# M903X.net
KiCad netlist of a schematic drawn in EAGLE
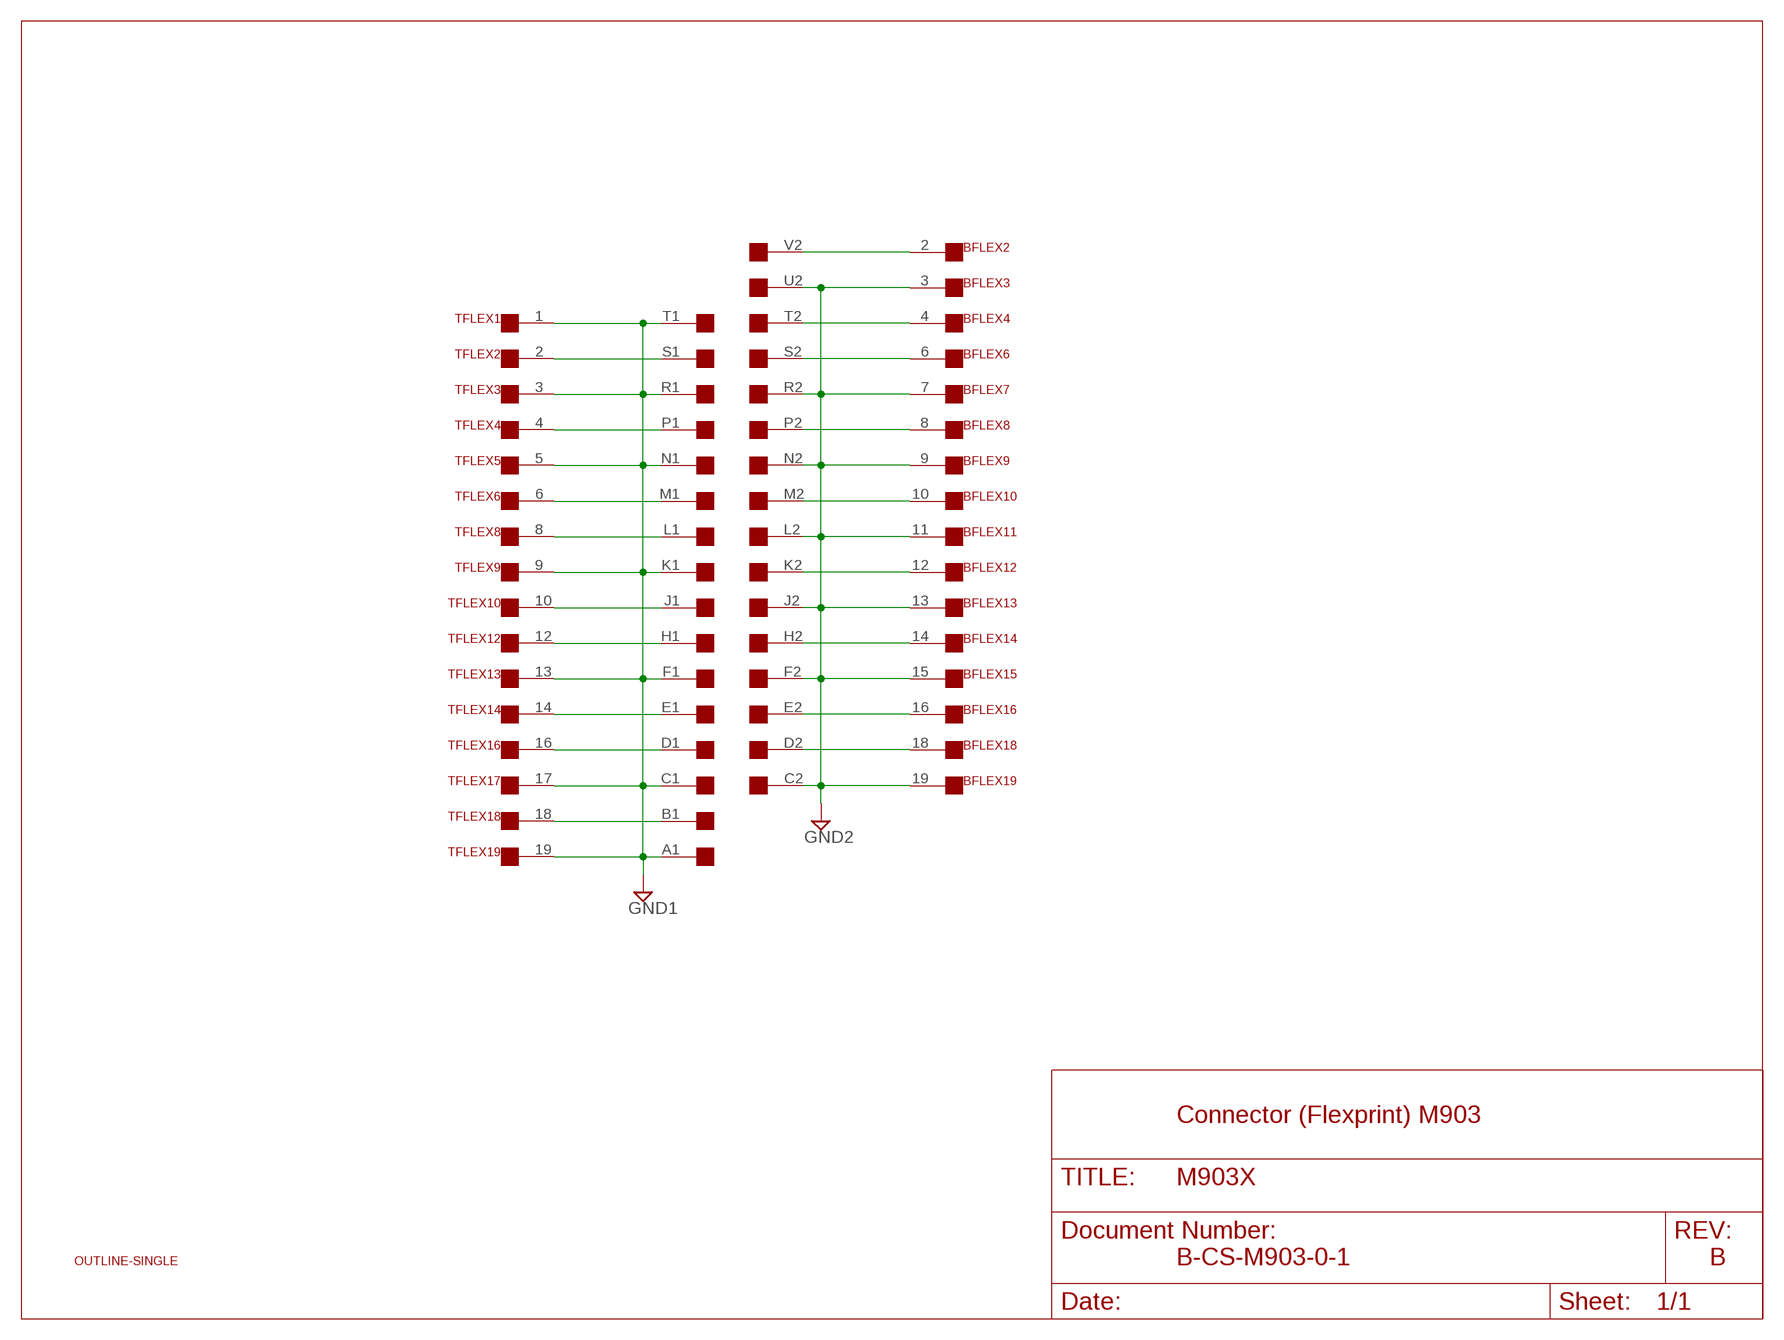
[diagram p0: schematic, sheet 1]

(export (version "E")
  (design (tool "Eeschema 10.0.6"))
  (components
    (comp (ref "BFLEX")
      (value "FLEX19")
      (footprint "eagle-import:FLEX19")
      (libsource (lib "eagle-import") (part "FLEX19"))
    )
    (comp (ref "TFLEX")
      (value "FLEX19")
      (footprint "eagle-import:FLEX19")
      (libsource (lib "eagle-import") (part "FLEX19"))
    )
    (comp (ref "U$1")
      (value "SINGLE")
      (footprint "eagle-import:EDGE-CON2")
      (libsource (lib "eagle-import") (part "SINGLE"))
    )
    (comp (ref "U$2")
      (value "OUTLINE-SINGLE")
      (footprint "eagle-import:SINGLE")
      (libsource (lib "eagle-import") (part "OUTLINE-SINGLE"))
    )
  )
  (nets
    (net (code "1") (name "GND1") (class "Default")
      (node (ref "TFLEX") (pin "1") (pinfunction "1_1") (pintype "passive"))
      (node (ref "TFLEX") (pin "13") (pinfunction "1_13") (pintype "passive"))
      (node (ref "TFLEX") (pin "17") (pinfunction "1_17") (pintype "passive"))
      (node (ref "TFLEX") (pin "19") (pinfunction "1_19") (pintype "passive"))
      (node (ref "TFLEX") (pin "3") (pinfunction "1_3") (pintype "passive"))
      (node (ref "TFLEX") (pin "5") (pinfunction "1_5") (pintype "passive"))
      (node (ref "TFLEX") (pin "9") (pinfunction "1_9") (pintype "passive"))
      (node (ref "U$1") (pin "A1") (pinfunction "1_A1") (pintype "bidirectional"))
      (node (ref "U$1") (pin "C1") (pinfunction "1_C1") (pintype "bidirectional"))
      (node (ref "U$1") (pin "F1") (pinfunction "1_F1") (pintype "bidirectional"))
      (node (ref "U$1") (pin "K1") (pinfunction "1_K1") (pintype "bidirectional"))
      (node (ref "U$1") (pin "N1") (pinfunction "1_N1") (pintype "bidirectional"))
      (node (ref "U$1") (pin "R1") (pinfunction "1_R1") (pintype "bidirectional"))
      (node (ref "U$1") (pin "T1") (pinfunction "1_T1") (pintype "bidirectional"))
    )
    (net (code "2") (name "GND2") (class "Default")
      (node (ref "BFLEX") (pin "11") (pinfunction "1_11") (pintype "passive"))
      (node (ref "BFLEX") (pin "13") (pinfunction "1_13") (pintype "passive"))
      (node (ref "BFLEX") (pin "15") (pinfunction "1_15") (pintype "passive"))
      (node (ref "BFLEX") (pin "19") (pinfunction "1_19") (pintype "passive"))
      (node (ref "BFLEX") (pin "3") (pinfunction "1_3") (pintype "passive"))
      (node (ref "BFLEX") (pin "7") (pinfunction "1_7") (pintype "passive"))
      (node (ref "BFLEX") (pin "9") (pinfunction "1_9") (pintype "passive"))
      (node (ref "U$1") (pin "C2") (pinfunction "1_C2") (pintype "bidirectional"))
      (node (ref "U$1") (pin "F2") (pinfunction "1_F2") (pintype "bidirectional"))
      (node (ref "U$1") (pin "J2") (pinfunction "1_J2") (pintype "bidirectional"))
      (node (ref "U$1") (pin "L2") (pinfunction "1_L2") (pintype "bidirectional"))
      (node (ref "U$1") (pin "N2") (pinfunction "1_N2") (pintype "bidirectional"))
      (node (ref "U$1") (pin "R2") (pinfunction "1_R2") (pintype "bidirectional"))
      (node (ref "U$1") (pin "U2") (pinfunction "1_U2") (pintype "bidirectional"))
    )
    (net (code "3") (name "Net-(BFLEXB-1)") (class "Default")
      (node (ref "BFLEX") (pin "10") (pinfunction "1_10") (pintype "passive"))
      (node (ref "U$1") (pin "M2") (pinfunction "1_M2") (pintype "bidirectional"))
    )
    (net (code "4") (name "Net-(BFLEXD-1)") (class "Default")
      (node (ref "BFLEX") (pin "12") (pinfunction "1_12") (pintype "passive"))
      (node (ref "U$1") (pin "K2") (pinfunction "1_K2") (pintype "bidirectional"))
    )
    (net (code "5") (name "Net-(BFLEXF-1)") (class "Default")
      (node (ref "BFLEX") (pin "14") (pinfunction "1_14") (pintype "passive"))
      (node (ref "U$1") (pin "H2") (pinfunction "1_H2") (pintype "bidirectional"))
    )
    (net (code "6") (name "Net-(BFLEXH-1)") (class "Default")
      (node (ref "BFLEX") (pin "16") (pinfunction "1_16") (pintype "passive"))
      (node (ref "U$1") (pin "E2") (pinfunction "1_E2") (pintype "bidirectional"))
    )
    (net (code "7") (name "Net-(BFLEXJ-1)") (class "Default")
      (node (ref "BFLEX") (pin "18") (pinfunction "1_18") (pintype "passive"))
      (node (ref "U$1") (pin "D2") (pinfunction "1_D2") (pintype "bidirectional"))
    )
    (net (code "8") (name "Net-(BFLEXL-1)") (class "Default")
      (node (ref "BFLEX") (pin "2") (pinfunction "1_2") (pintype "passive"))
      (node (ref "U$1") (pin "V2") (pinfunction "1_V2") (pintype "bidirectional"))
    )
    (net (code "9") (name "Net-(BFLEXN-1)") (class "Default")
      (node (ref "BFLEX") (pin "4") (pinfunction "1_4") (pintype "passive"))
      (node (ref "U$1") (pin "T2") (pinfunction "1_T2") (pintype "bidirectional"))
    )
    (net (code "10") (name "Net-(BFLEXP-1)") (class "Default")
      (node (ref "BFLEX") (pin "6") (pinfunction "1_6") (pintype "passive"))
      (node (ref "U$1") (pin "S2") (pinfunction "1_S2") (pintype "bidirectional"))
    )
    (net (code "11") (name "Net-(BFLEXR-1)") (class "Default")
      (node (ref "BFLEX") (pin "8") (pinfunction "1_8") (pintype "passive"))
      (node (ref "U$1") (pin "P2") (pinfunction "1_P2") (pintype "bidirectional"))
    )
    (net (code "12") (name "Net-(TFLEXB-1)") (class "Default")
      (node (ref "TFLEX") (pin "10") (pinfunction "1_10") (pintype "passive"))
      (node (ref "U$1") (pin "J1") (pinfunction "1_J1") (pintype "bidirectional"))
    )
    (net (code "13") (name "Net-(TFLEXD-1)") (class "Default")
      (node (ref "TFLEX") (pin "12") (pinfunction "1_12") (pintype "passive"))
      (node (ref "U$1") (pin "H1") (pinfunction "1_H1") (pintype "bidirectional"))
    )
    (net (code "14") (name "Net-(TFLEXF-1)") (class "Default")
      (node (ref "TFLEX") (pin "14") (pinfunction "1_14") (pintype "passive"))
      (node (ref "U$1") (pin "E1") (pinfunction "1_E1") (pintype "bidirectional"))
    )
    (net (code "15") (name "Net-(TFLEXH-1)") (class "Default")
      (node (ref "TFLEX") (pin "16") (pinfunction "1_16") (pintype "passive"))
      (node (ref "U$1") (pin "D1") (pinfunction "1_D1") (pintype "bidirectional"))
    )
    (net (code "16") (name "Net-(TFLEXJ-1)") (class "Default")
      (node (ref "TFLEX") (pin "18") (pinfunction "1_18") (pintype "passive"))
      (node (ref "U$1") (pin "B1") (pinfunction "1_B1") (pintype "bidirectional"))
    )
    (net (code "17") (name "Net-(TFLEXL-1)") (class "Default")
      (node (ref "TFLEX") (pin "2") (pinfunction "1_2") (pintype "passive"))
      (node (ref "U$1") (pin "S1") (pinfunction "1_S1") (pintype "bidirectional"))
    )
    (net (code "18") (name "Net-(TFLEXN-1)") (class "Default")
      (node (ref "TFLEX") (pin "4") (pinfunction "1_4") (pintype "passive"))
      (node (ref "U$1") (pin "P1") (pinfunction "1_P1") (pintype "bidirectional"))
    )
    (net (code "19") (name "Net-(TFLEXP-1)") (class "Default")
      (node (ref "TFLEX") (pin "6") (pinfunction "1_6") (pintype "passive"))
      (node (ref "U$1") (pin "M1") (pinfunction "1_M1") (pintype "bidirectional"))
    )
    (net (code "20") (name "Net-(TFLEXR-1)") (class "Default")
      (node (ref "TFLEX") (pin "8") (pinfunction "1_8") (pintype "passive"))
      (node (ref "U$1") (pin "L1") (pinfunction "1_L1") (pintype "bidirectional"))
    )
  )
)
